# CPU_LPDDR4.net
KiCad netlist of a schematic drawn in Altium Designer
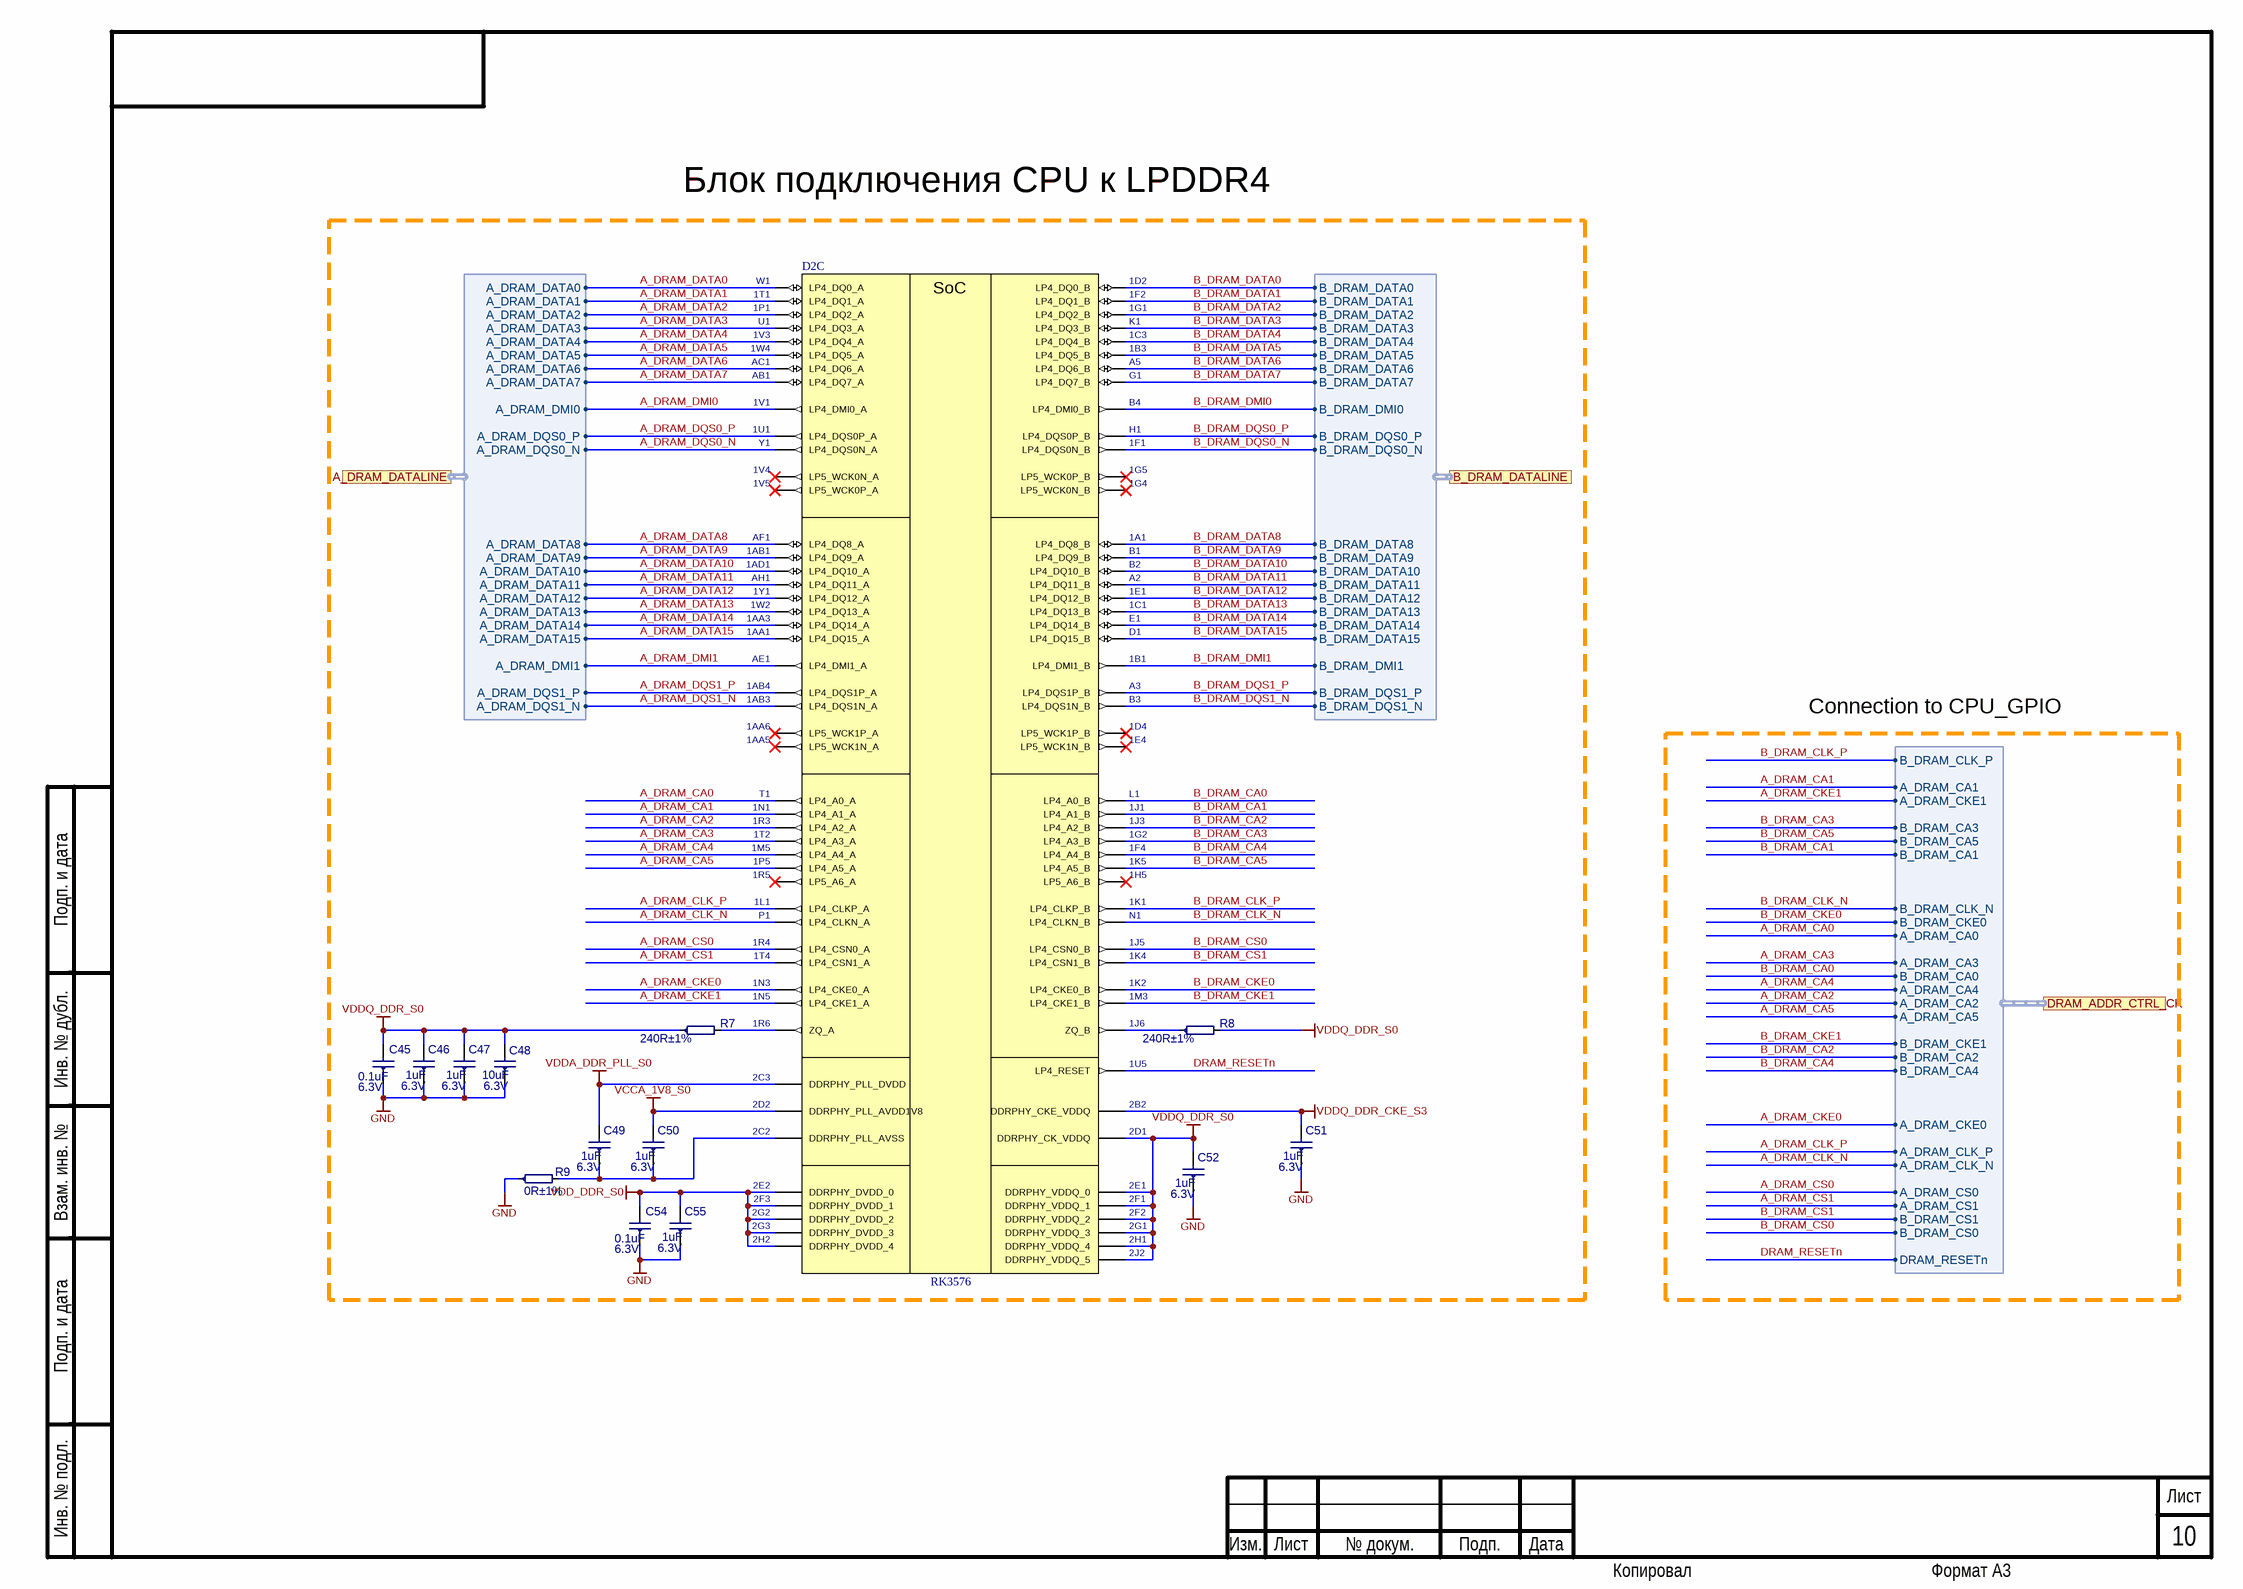
[diagram p0: CPU_LPDDR4.SchDoc]

(export (version "E")
  (design (tool "Eeschema 10.0.6"))
  (components
    (comp (ref "C45")
      (value "0.1uF")
      (footprint "C0201")
      (fields
        (field (name "VOLTAGE") "6.3V")
        (field (name "PART NUMBER") "0201-X5R-6.3V-0.1uF±10%")
        (field (name "TOLERANCE") "10%")
        (field (name "MANUFACTURER") "Yageo")
      )
      (libsource (lib "ATB") (part "C"))
    )
    (comp (ref "C46")
      (value "1uF")
      (footprint "C0201")
      (fields
        (field (name "VOLTAGE") "6.3V")
        (field (name "PART NUMBER") "0201-X5R-6.3V-1uF±20%")
        (field (name "TOLERANCE") "20%")
        (field (name "MANUFACTURER") "Murata Electronics")
      )
      (libsource (lib "ATB") (part "C"))
    )
    (comp (ref "C47")
      (value "1uF")
      (footprint "C0201")
      (fields
        (field (name "VOLTAGE") "6.3V")
        (field (name "PART NUMBER") "0201-X5R-6.3V-1uF±20%")
        (field (name "TOLERANCE") "20%")
        (field (name "MANUFACTURER") "Murata Electronics")
      )
      (libsource (lib "ATB") (part "C"))
    )
    (comp (ref "C48")
      (value "10uF")
      (footprint "C0402")
      (fields
        (field (name "VOLTAGE") "6.3V")
        (field (name "PART NUMBER") "0402-X5R-6.3V-10uF±20%")
        (field (name "TOLERANCE") "20%")
        (field (name "MANUFACTURER") "Yageo")
      )
      (libsource (lib "ATB") (part "C"))
    )
    (comp (ref "C49")
      (value "1uF")
      (footprint "C0201")
      (fields
        (field (name "VOLTAGE") "6.3V")
        (field (name "PART NUMBER") "0201-X5R-6.3V-1uF±20%")
        (field (name "TOLERANCE") "20%")
        (field (name "MANUFACTURER") "Murata Electronics")
      )
      (libsource (lib "ATB") (part "C"))
    )
    (comp (ref "C50")
      (value "1uF")
      (footprint "C0201")
      (fields
        (field (name "VOLTAGE") "6.3V")
        (field (name "PART NUMBER") "0201-X5R-6.3V-1uF±20%")
        (field (name "TOLERANCE") "20%")
        (field (name "MANUFACTURER") "Murata Electronics")
      )
      (libsource (lib "ATB") (part "C"))
    )
    (comp (ref "C51")
      (value "1uF")
      (footprint "C0201")
      (fields
        (field (name "VOLTAGE") "6.3V")
        (field (name "PART NUMBER") "0201-X5R-6.3V-1uF±20%")
        (field (name "TOLERANCE") "20%")
        (field (name "MANUFACTURER") "Murata Electronics")
      )
      (libsource (lib "ATB") (part "C"))
    )
    (comp (ref "C52")
      (value "1uF")
      (footprint "C0201")
      (fields
        (field (name "VOLTAGE") "6.3V")
        (field (name "PART NUMBER") "0201-X5R-6.3V-1uF±20%")
        (field (name "TOLERANCE") "20%")
        (field (name "MANUFACTURER") "Murata Electronics")
      )
      (libsource (lib "ATB") (part "C"))
    )
    (comp (ref "C54")
      (value "0.1uF")
      (footprint "C0201")
      (fields
        (field (name "VOLTAGE") "6.3V")
        (field (name "PART NUMBER") "0201-X5R-6.3V-0.1uF±10%")
        (field (name "TOLERANCE") "10%")
        (field (name "MANUFACTURER") "Yageo")
      )
      (libsource (lib "ATB") (part "C"))
    )
    (comp (ref "C55")
      (value "1uF")
      (footprint "C0201")
      (fields
        (field (name "VOLTAGE") "6.3V")
        (field (name "PART NUMBER") "0201-X5R-6.3V-1uF±20%")
        (field (name "TOLERANCE") "20%")
        (field (name "MANUFACTURER") "Murata Electronics")
      )
      (libsource (lib "ATB") (part "C"))
    )
    (comp (ref "D2")
      (value "RK3576")
      (footprint "BGAFCCSP698L")
      (description "SoC 4xCortex-A72@2.2Ghz+4xCortex-A53@2Ghz, LPDDR4/4X/5/5X, SDIO/eMMC/UFS/FSPI, BGA 16.1x17.2x1.0mm")
      (fields (field (name "MANUFACTURER") "Rockship"))
      (libsource (lib "ATB") (part "RK3576"))
    )
    (comp (ref "R7")
      (value "240R±1%")
      (footprint "R0201")
      (fields
        (field (name "PART NUMBER") "0201-0.05W-240R-100ppm-5%")
        (field (name "TOLERANCE") "1%")
        (field (name "MANUFACTURER") "Yageo")
      )
      (libsource (lib "ATB") (part "R"))
    )
    (comp (ref "R8")
      (value "240R±1%")
      (footprint "R0201")
      (fields
        (field (name "PART NUMBER") "0201-0.05W-240R-100ppm-5%")
        (field (name "TOLERANCE") "1%")
        (field (name "MANUFACTURER") "Yageo")
      )
      (libsource (lib "ATB") (part "R"))
    )
    (comp (ref "R9")
      (value "0R±1%")
      (footprint "R0402")
      (description "Chip Resistor 0402 0Ω ±1% 50V ±100ppm/℃ Thick Film")
      (fields (field (name "PART NUMBER") "0402-0.0625W-0R-100ppm±1%") (field (name "TOLERANCE") "1%"))
      (libsource (lib "ATB") (part "R"))
    )
  )
  (nets
    (net (code "4") (name "/A_DRAM_CA0") (class "Default")
      (node (ref "D2") (pin "T1") (pinfunction "LP4_A0_A_T1") (pintype "output"))
    )
    (net (code "5") (name "/A_DRAM_CA1") (class "Default")
      (node (ref "D2") (pin "1N1") (pinfunction "LP4_A1_A_1N1") (pintype "output"))
    )
    (net (code "6") (name "/A_DRAM_CA2") (class "Default")
      (node (ref "D2") (pin "1R3") (pinfunction "LP4_A2_A_1R3") (pintype "output"))
    )
    (net (code "7") (name "/A_DRAM_CA3") (class "Default")
      (node (ref "D2") (pin "1T2") (pinfunction "LP4_A3_A_1T2") (pintype "output"))
    )
    (net (code "8") (name "/A_DRAM_CA4") (class "Default")
      (node (ref "D2") (pin "1M5") (pinfunction "LP4_A4_A_1M5") (pintype "output"))
    )
    (net (code "9") (name "/A_DRAM_CA5") (class "Default")
      (node (ref "D2") (pin "1P5") (pinfunction "LP4_A5_A_1P5") (pintype "output"))
    )
    (net (code "10") (name "/A_DRAM_CKE0") (class "Default")
      (node (ref "D2") (pin "1N3") (pinfunction "LP4_CKE0_A_1N3") (pintype "output"))
    )
    (net (code "11") (name "/A_DRAM_CKE1") (class "Default")
      (node (ref "D2") (pin "1N5") (pinfunction "LP4_CKE1_A_1N5") (pintype "output"))
    )
    (net (code "12") (name "/A_DRAM_CLK_N") (class "Default")
      (node (ref "D2") (pin "P1") (pinfunction "LP4_CLKN_A_P1") (pintype "output"))
    )
    (net (code "13") (name "/A_DRAM_CLK_P") (class "Default")
      (node (ref "D2") (pin "1L1") (pinfunction "LP4_CLKP_A_1L1") (pintype "output"))
    )
    (net (code "14") (name "/A_DRAM_CS0") (class "Default")
      (node (ref "D2") (pin "1R4") (pinfunction "LP4_CSN0_A_1R4") (pintype "output"))
    )
    (net (code "15") (name "/A_DRAM_CS1") (class "Default")
      (node (ref "D2") (pin "1T4") (pinfunction "LP4_CSN1_A_1T4") (pintype "output"))
    )
    (net (code "16") (name "/A_DRAM_DATA0") (class "Default")
      (node (ref "D2") (pin "W1") (pinfunction "LP4_DQ0_A_W1") (pintype "bidirectional"))
    )
    (net (code "17") (name "/A_DRAM_DATA1") (class "Default")
      (node (ref "D2") (pin "1T1") (pinfunction "LP4_DQ1_A_1T1") (pintype "bidirectional"))
    )
    (net (code "18") (name "/A_DRAM_DATA2") (class "Default")
      (node (ref "D2") (pin "1P1") (pinfunction "LP4_DQ2_A_1P1") (pintype "bidirectional"))
    )
    (net (code "19") (name "/A_DRAM_DATA3") (class "Default")
      (node (ref "D2") (pin "U1") (pinfunction "LP4_DQ3_A_U1") (pintype "bidirectional"))
    )
    (net (code "20") (name "/A_DRAM_DATA4") (class "Default")
      (node (ref "D2") (pin "1V3") (pinfunction "LP4_DQ4_A_1V3") (pintype "bidirectional"))
    )
    (net (code "21") (name "/A_DRAM_DATA5") (class "Default")
      (node (ref "D2") (pin "1W4") (pinfunction "LP4_DQ5_A_1W4") (pintype "bidirectional"))
    )
    (net (code "22") (name "/A_DRAM_DATA6") (class "Default")
      (node (ref "D2") (pin "AC1") (pinfunction "LP4_DQ6_A_AC1") (pintype "bidirectional"))
    )
    (net (code "23") (name "/A_DRAM_DATA7") (class "Default")
      (node (ref "D2") (pin "AB1") (pinfunction "LP4_DQ7_A_AB1") (pintype "bidirectional"))
    )
    (net (code "24") (name "/A_DRAM_DATA8") (class "Default")
      (node (ref "D2") (pin "AF1") (pinfunction "LP4_DQ8_A_AF1") (pintype "bidirectional"))
    )
    (net (code "25") (name "/A_DRAM_DATA9") (class "Default")
      (node (ref "D2") (pin "1AB1") (pinfunction "LP4_DQ9_A_1AB1") (pintype "bidirectional"))
    )
    (net (code "26") (name "/A_DRAM_DATA10") (class "Default")
      (node (ref "D2") (pin "1AD1") (pinfunction "LP4_DQ10_A_1AD1") (pintype "bidirectional"))
    )
    (net (code "27") (name "/A_DRAM_DATA11") (class "Default")
      (node (ref "D2") (pin "AH1") (pinfunction "LP4_DQ11_A_AH1") (pintype "bidirectional"))
    )
    (net (code "28") (name "/A_DRAM_DATA12") (class "Default")
      (node (ref "D2") (pin "1Y1") (pinfunction "LP4_DQ12_A_1Y1") (pintype "bidirectional"))
    )
    (net (code "29") (name "/A_DRAM_DATA13") (class "Default")
      (node (ref "D2") (pin "1W2") (pinfunction "LP4_DQ13_A_1W2") (pintype "bidirectional"))
    )
    (net (code "30") (name "/A_DRAM_DATA14") (class "Default")
      (node (ref "D2") (pin "1AA3") (pinfunction "LP4_DQ14_A_1AA3") (pintype "bidirectional"))
    )
    (net (code "31") (name "/A_DRAM_DATA15") (class "Default")
      (node (ref "D2") (pin "1AA1") (pinfunction "LP4_DQ15_A_1AA1") (pintype "bidirectional"))
    )
    (net (code "32") (name "/A_DRAM_DMI0") (class "Default")
      (node (ref "D2") (pin "1V1") (pinfunction "LP4_DMI0_A_1V1") (pintype "output"))
    )
    (net (code "33") (name "/A_DRAM_DMI1") (class "Default")
      (node (ref "D2") (pin "AE1") (pinfunction "LP4_DMI1_A_AE1") (pintype "output"))
    )
    (net (code "34") (name "/A_DRAM_DQS0_N") (class "Default")
      (node (ref "D2") (pin "Y1") (pinfunction "LP4_DQS0N_A_Y1") (pintype "output"))
    )
    (net (code "35") (name "/A_DRAM_DQS0_P") (class "Default")
      (node (ref "D2") (pin "1U1") (pinfunction "LP4_DQS0P_A_1U1") (pintype "output"))
    )
    (net (code "36") (name "/A_DRAM_DQS1_N") (class "Default")
      (node (ref "D2") (pin "1AB3") (pinfunction "LP4_DQS1N_A_1AB3") (pintype "output"))
    )
    (net (code "37") (name "/A_DRAM_DQS1_P") (class "Default")
      (node (ref "D2") (pin "1AB4") (pinfunction "LP4_DQS1P_A_1AB4") (pintype "output"))
    )
    (net (code "38") (name "/B_DRAM_CA0") (class "Default")
      (node (ref "D2") (pin "L1") (pinfunction "LP4_A0_B_L1") (pintype "output"))
    )
    (net (code "39") (name "/B_DRAM_CA1") (class "Default")
      (node (ref "D2") (pin "1J1") (pinfunction "LP4_A1_B_1J1") (pintype "output"))
    )
    (net (code "40") (name "/B_DRAM_CA2") (class "Default")
      (node (ref "D2") (pin "1J3") (pinfunction "LP4_A2_B_1J3") (pintype "output"))
    )
    (net (code "41") (name "/B_DRAM_CA3") (class "Default")
      (node (ref "D2") (pin "1G2") (pinfunction "LP4_A3_B_1G2") (pintype "output"))
    )
    (net (code "42") (name "/B_DRAM_CA4") (class "Default")
      (node (ref "D2") (pin "1F4") (pinfunction "LP4_A4_B_1F4") (pintype "output"))
    )
    (net (code "43") (name "/B_DRAM_CA5") (class "Default")
      (node (ref "D2") (pin "1K5") (pinfunction "LP4_A5_B_1K5") (pintype "output"))
    )
    (net (code "44") (name "/B_DRAM_CKE0") (class "Default")
      (node (ref "D2") (pin "1K2") (pinfunction "LP4_CKE0_B_1K2") (pintype "output"))
    )
    (net (code "45") (name "/B_DRAM_CKE1") (class "Default")
      (node (ref "D2") (pin "1M3") (pinfunction "LP4_CKE1_B_1M3") (pintype "output"))
    )
    (net (code "46") (name "/B_DRAM_CLK_N") (class "Default")
      (node (ref "D2") (pin "N1") (pinfunction "LP4_CLKN_B_N1") (pintype "output"))
    )
    (net (code "47") (name "/B_DRAM_CLK_P") (class "Default")
      (node (ref "D2") (pin "1K1") (pinfunction "LP4_CLKP_B_1K1") (pintype "output"))
    )
    (net (code "48") (name "/B_DRAM_CS0") (class "Default")
      (node (ref "D2") (pin "1J5") (pinfunction "LP4_CSN0_B_1J5") (pintype "output"))
    )
    (net (code "49") (name "/B_DRAM_CS1") (class "Default")
      (node (ref "D2") (pin "1K4") (pinfunction "LP4_CSN1_B_1K4") (pintype "output"))
    )
    (net (code "50") (name "/B_DRAM_DATA0") (class "Default")
      (node (ref "D2") (pin "1D2") (pinfunction "LP4_DQ0_B_1D2") (pintype "bidirectional"))
    )
    (net (code "51") (name "/B_DRAM_DATA1") (class "Default")
      (node (ref "D2") (pin "1F2") (pinfunction "LP4_DQ1_B_1F2") (pintype "bidirectional"))
    )
    (net (code "52") (name "/B_DRAM_DATA2") (class "Default")
      (node (ref "D2") (pin "1G1") (pinfunction "LP4_DQ2_B_1G1") (pintype "bidirectional"))
    )
    (net (code "53") (name "/B_DRAM_DATA3") (class "Default")
      (node (ref "D2") (pin "K1") (pinfunction "LP4_DQ3_B_K1") (pintype "bidirectional"))
    )
    (net (code "54") (name "/B_DRAM_DATA4") (class "Default")
      (node (ref "D2") (pin "1C3") (pinfunction "LP4_DQ4_B_1C3") (pintype "bidirectional"))
    )
    (net (code "55") (name "/B_DRAM_DATA5") (class "Default")
      (node (ref "D2") (pin "1B3") (pinfunction "LP4_DQ5_B_1B3") (pintype "bidirectional"))
    )
    (net (code "56") (name "/B_DRAM_DATA6") (class "Default")
      (node (ref "D2") (pin "A5") (pinfunction "LP4_DQ6_B_A5") (pintype "bidirectional"))
    )
    (net (code "57") (name "/B_DRAM_DATA7") (class "Default")
      (node (ref "D2") (pin "G1") (pinfunction "LP4_DQ7_B_G1") (pintype "bidirectional"))
    )
    (net (code "58") (name "/B_DRAM_DATA8") (class "Default")
      (node (ref "D2") (pin "1A1") (pinfunction "LP4_DQ8_B_1A1") (pintype "bidirectional"))
    )
    (net (code "59") (name "/B_DRAM_DATA9") (class "Default")
      (node (ref "D2") (pin "B1") (pinfunction "LP4_DQ9_B_B1") (pintype "bidirectional"))
    )
    (net (code "60") (name "/B_DRAM_DATA10") (class "Default")
      (node (ref "D2") (pin "B2") (pinfunction "LP4_DQ10_B_B2") (pintype "bidirectional"))
    )
    (net (code "61") (name "/B_DRAM_DATA11") (class "Default")
      (node (ref "D2") (pin "A2") (pinfunction "LP4_DQ11_B_A2") (pintype "bidirectional"))
    )
    (net (code "62") (name "/B_DRAM_DATA12") (class "Default")
      (node (ref "D2") (pin "1E1") (pinfunction "LP4_DQ12_B_1E1") (pintype "bidirectional"))
    )
    (net (code "63") (name "/B_DRAM_DATA13") (class "Default")
      (node (ref "D2") (pin "1C1") (pinfunction "LP4_DQ13_B_1C1") (pintype "bidirectional"))
    )
    (net (code "64") (name "/B_DRAM_DATA14") (class "Default")
      (node (ref "D2") (pin "E1") (pinfunction "LP4_DQ14_B_E1") (pintype "bidirectional"))
    )
    (net (code "65") (name "/B_DRAM_DATA15") (class "Default")
      (node (ref "D2") (pin "D1") (pinfunction "LP4_DQ15_B_D1") (pintype "bidirectional"))
    )
    (net (code "66") (name "/B_DRAM_DMI0") (class "Default")
      (node (ref "D2") (pin "B4") (pinfunction "LP4_DMI0_B_B4") (pintype "output"))
    )
    (net (code "67") (name "/B_DRAM_DMI1") (class "Default")
      (node (ref "D2") (pin "1B1") (pinfunction "LP4_DMI1_B_1B1") (pintype "output"))
    )
    (net (code "68") (name "/B_DRAM_DQS0_N") (class "Default")
      (node (ref "D2") (pin "1F1") (pinfunction "LP4_DQS0N_B_1F1") (pintype "output"))
    )
    (net (code "69") (name "/B_DRAM_DQS0_P") (class "Default")
      (node (ref "D2") (pin "H1") (pinfunction "LP4_DQS0P_B_H1") (pintype "output"))
    )
    (net (code "70") (name "/B_DRAM_DQS1_N") (class "Default")
      (node (ref "D2") (pin "B3") (pinfunction "LP4_DQS1N_B_B3") (pintype "output"))
    )
    (net (code "71") (name "/B_DRAM_DQS1_P") (class "Default")
      (node (ref "D2") (pin "A3") (pinfunction "LP4_DQS1P_B_A3") (pintype "output"))
    )
    (net (code "72") (name "/DRAM_RESETn") (class "Default")
      (node (ref "D2") (pin "1U5") (pinfunction "LP4_RESET_1U5") (pintype "output"))
    )
    (net (code "76") (name "GND") (class "Default")
      (node (ref "C45") (pin "1") (pinfunction "1_1") (pintype "passive"))
      (node (ref "C46") (pin "1") (pinfunction "1_1") (pintype "passive"))
      (node (ref "C47") (pin "1") (pinfunction "1_1") (pintype "passive"))
      (node (ref "C48") (pin "1") (pinfunction "1_1") (pintype "passive"))
      (node (ref "C51") (pin "1") (pinfunction "1_1") (pintype "passive"))
      (node (ref "C52") (pin "1") (pinfunction "1_1") (pintype "passive"))
      (node (ref "C54") (pin "1") (pinfunction "1_1") (pintype "passive"))
      (node (ref "C55") (pin "1") (pinfunction "1_1") (pintype "passive"))
      (node (ref "R9") (pin "1") (pinfunction "1_1") (pintype "passive"))
    )
    (net (code "77") (name "Net-(D2C-DDRPHY_PLL_AVSS)") (class "Default")
      (node (ref "C49") (pin "1") (pinfunction "1_1") (pintype "passive"))
      (node (ref "C50") (pin "1") (pinfunction "1_1") (pintype "passive"))
      (node (ref "D2") (pin "2C2") (pinfunction "DDRPHY_PLL_AVSS_2C2") (pintype "power_in"))
      (node (ref "R9") (pin "2") (pinfunction "2_2") (pintype "passive"))
    )
    (net (code "78") (name "Net-(D2C-ZQ_A)") (class "Default")
      (node (ref "D2") (pin "1R6") (pinfunction "ZQ_A_1R6") (pintype "output"))
      (node (ref "R7") (pin "2") (pinfunction "2_2") (pintype "passive"))
    )
    (net (code "79") (name "Net-(D2C-ZQ_B)") (class "Default")
      (node (ref "D2") (pin "1J6") (pinfunction "ZQ_B_1J6") (pintype "output"))
      (node (ref "R8") (pin "1") (pinfunction "1_1") (pintype "passive"))
    )
    (net (code "80") (name "VCCA_1V8_S0") (class "Default")
      (node (ref "C50") (pin "2") (pinfunction "2_2") (pintype "passive"))
      (node (ref "D2") (pin "2D2") (pinfunction "DDRPHY_PLL_AVDD1V8_2D2") (pintype "power_in"))
    )
    (net (code "81") (name "VDDA_DDR_PLL_S0") (class "Default")
      (node (ref "C49") (pin "2") (pinfunction "2_2") (pintype "passive"))
      (node (ref "D2") (pin "2C3") (pinfunction "DDRPHY_PLL_DVDD_2C3") (pintype "power_in"))
    )
    (net (code "82") (name "VDDQ_DDR_CKE_S3") (class "Default")
      (node (ref "C51") (pin "2") (pinfunction "2_2") (pintype "passive"))
      (node (ref "D2") (pin "2B2") (pinfunction "DDRPHY_CKE_VDDQ_2B2") (pintype "power_in"))
    )
    (net (code "83") (name "VDDQ_DDR_S0") (class "Default")
      (node (ref "C45") (pin "2") (pinfunction "2_2") (pintype "passive"))
      (node (ref "C46") (pin "2") (pinfunction "2_2") (pintype "passive"))
      (node (ref "C47") (pin "2") (pinfunction "2_2") (pintype "passive"))
      (node (ref "C48") (pin "2") (pinfunction "2_2") (pintype "passive"))
      (node (ref "C52") (pin "2") (pinfunction "2_2") (pintype "passive"))
      (node (ref "D2") (pin "2D1") (pinfunction "DDRPHY_CK_VDDQ_2D1") (pintype "power_in"))
      (node (ref "D2") (pin "2E1") (pinfunction "DDRPHY_VDDQ_0_2E1") (pintype "power_in"))
      (node (ref "D2") (pin "2F1") (pinfunction "DDRPHY_VDDQ_1_2F1") (pintype "power_in"))
      (node (ref "D2") (pin "2F2") (pinfunction "DDRPHY_VDDQ_2_2F2") (pintype "power_in"))
      (node (ref "D2") (pin "2G1") (pinfunction "DDRPHY_VDDQ_3_2G1") (pintype "power_in"))
      (node (ref "D2") (pin "2H1") (pinfunction "DDRPHY_VDDQ_4_2H1") (pintype "power_in"))
      (node (ref "D2") (pin "2J2") (pinfunction "DDRPHY_VDDQ_5_2J2") (pintype "power_in"))
      (node (ref "R7") (pin "1") (pinfunction "1_1") (pintype "passive"))
      (node (ref "R8") (pin "2") (pinfunction "2_2") (pintype "passive"))
    )
    (net (code "84") (name "VDD_DDR_S0") (class "Default")
      (node (ref "C54") (pin "2") (pinfunction "2_2") (pintype "passive"))
      (node (ref "C55") (pin "2") (pinfunction "2_2") (pintype "passive"))
      (node (ref "D2") (pin "2E2") (pinfunction "DDRPHY_DVDD_0_2E2") (pintype "power_in"))
      (node (ref "D2") (pin "2F3") (pinfunction "DDRPHY_DVDD_1_2F3") (pintype "power_in"))
      (node (ref "D2") (pin "2G2") (pinfunction "DDRPHY_DVDD_2_2G2") (pintype "power_in"))
      (node (ref "D2") (pin "2G3") (pinfunction "DDRPHY_DVDD_3_2G3") (pintype "power_in"))
      (node (ref "D2") (pin "2H2") (pinfunction "DDRPHY_DVDD_4_2H2") (pintype "power_in"))
    )
    (net (code "85") (name "unconnected-(D2C-LP5_A6_A-Pad1R5)") (class "Default")
      (node (ref "D2") (pin "1R5") (pinfunction "LP5_A6_A_1R5") (pintype "output+no_connect"))
    )
    (net (code "86") (name "unconnected-(D2C-LP5_A6_B-Pad1H5)") (class "Default")
      (node (ref "D2") (pin "1H5") (pinfunction "LP5_A6_B_1H5") (pintype "output+no_connect"))
    )
    (net (code "87") (name "unconnected-(D2C-LP5_WCK0N_A-Pad1V4)") (class "Default")
      (node (ref "D2") (pin "1V4") (pinfunction "LP5_WCK0N_A_1V4") (pintype "output+no_connect"))
    )
    (net (code "88") (name "unconnected-(D2C-LP5_WCK0N_B-Pad1G4)") (class "Default")
      (node (ref "D2") (pin "1G4") (pinfunction "LP5_WCK0N_B_1G4") (pintype "output+no_connect"))
    )
    (net (code "89") (name "unconnected-(D2C-LP5_WCK0P_A-Pad1V5)") (class "Default")
      (node (ref "D2") (pin "1V5") (pinfunction "LP5_WCK0P_A_1V5") (pintype "output+no_connect"))
    )
    (net (code "90") (name "unconnected-(D2C-LP5_WCK0P_B-Pad1G5)") (class "Default")
      (node (ref "D2") (pin "1G5") (pinfunction "LP5_WCK0P_B_1G5") (pintype "output+no_connect"))
    )
    (net (code "91") (name "unconnected-(D2C-LP5_WCK1N_A-Pad1AA5)") (class "Default")
      (node (ref "D2") (pin "1AA5") (pinfunction "LP5_WCK1N_A_1AA5") (pintype "output+no_connect"))
    )
    (net (code "92") (name "unconnected-(D2C-LP5_WCK1N_B-Pad1E4)") (class "Default")
      (node (ref "D2") (pin "1E4") (pinfunction "LP5_WCK1N_B_1E4") (pintype "output+no_connect"))
    )
    (net (code "93") (name "unconnected-(D2C-LP5_WCK1P_A-Pad1AA6)") (class "Default")
      (node (ref "D2") (pin "1AA6") (pinfunction "LP5_WCK1P_A_1AA6") (pintype "output+no_connect"))
    )
    (net (code "94") (name "unconnected-(D2C-LP5_WCK1P_B-Pad1D4)") (class "Default")
      (node (ref "D2") (pin "1D4") (pinfunction "LP5_WCK1P_B_1D4") (pintype "output+no_connect"))
    )
  )
)
